# RM_finish.net
KiCad netlist of a schematic drawn in EAGLE
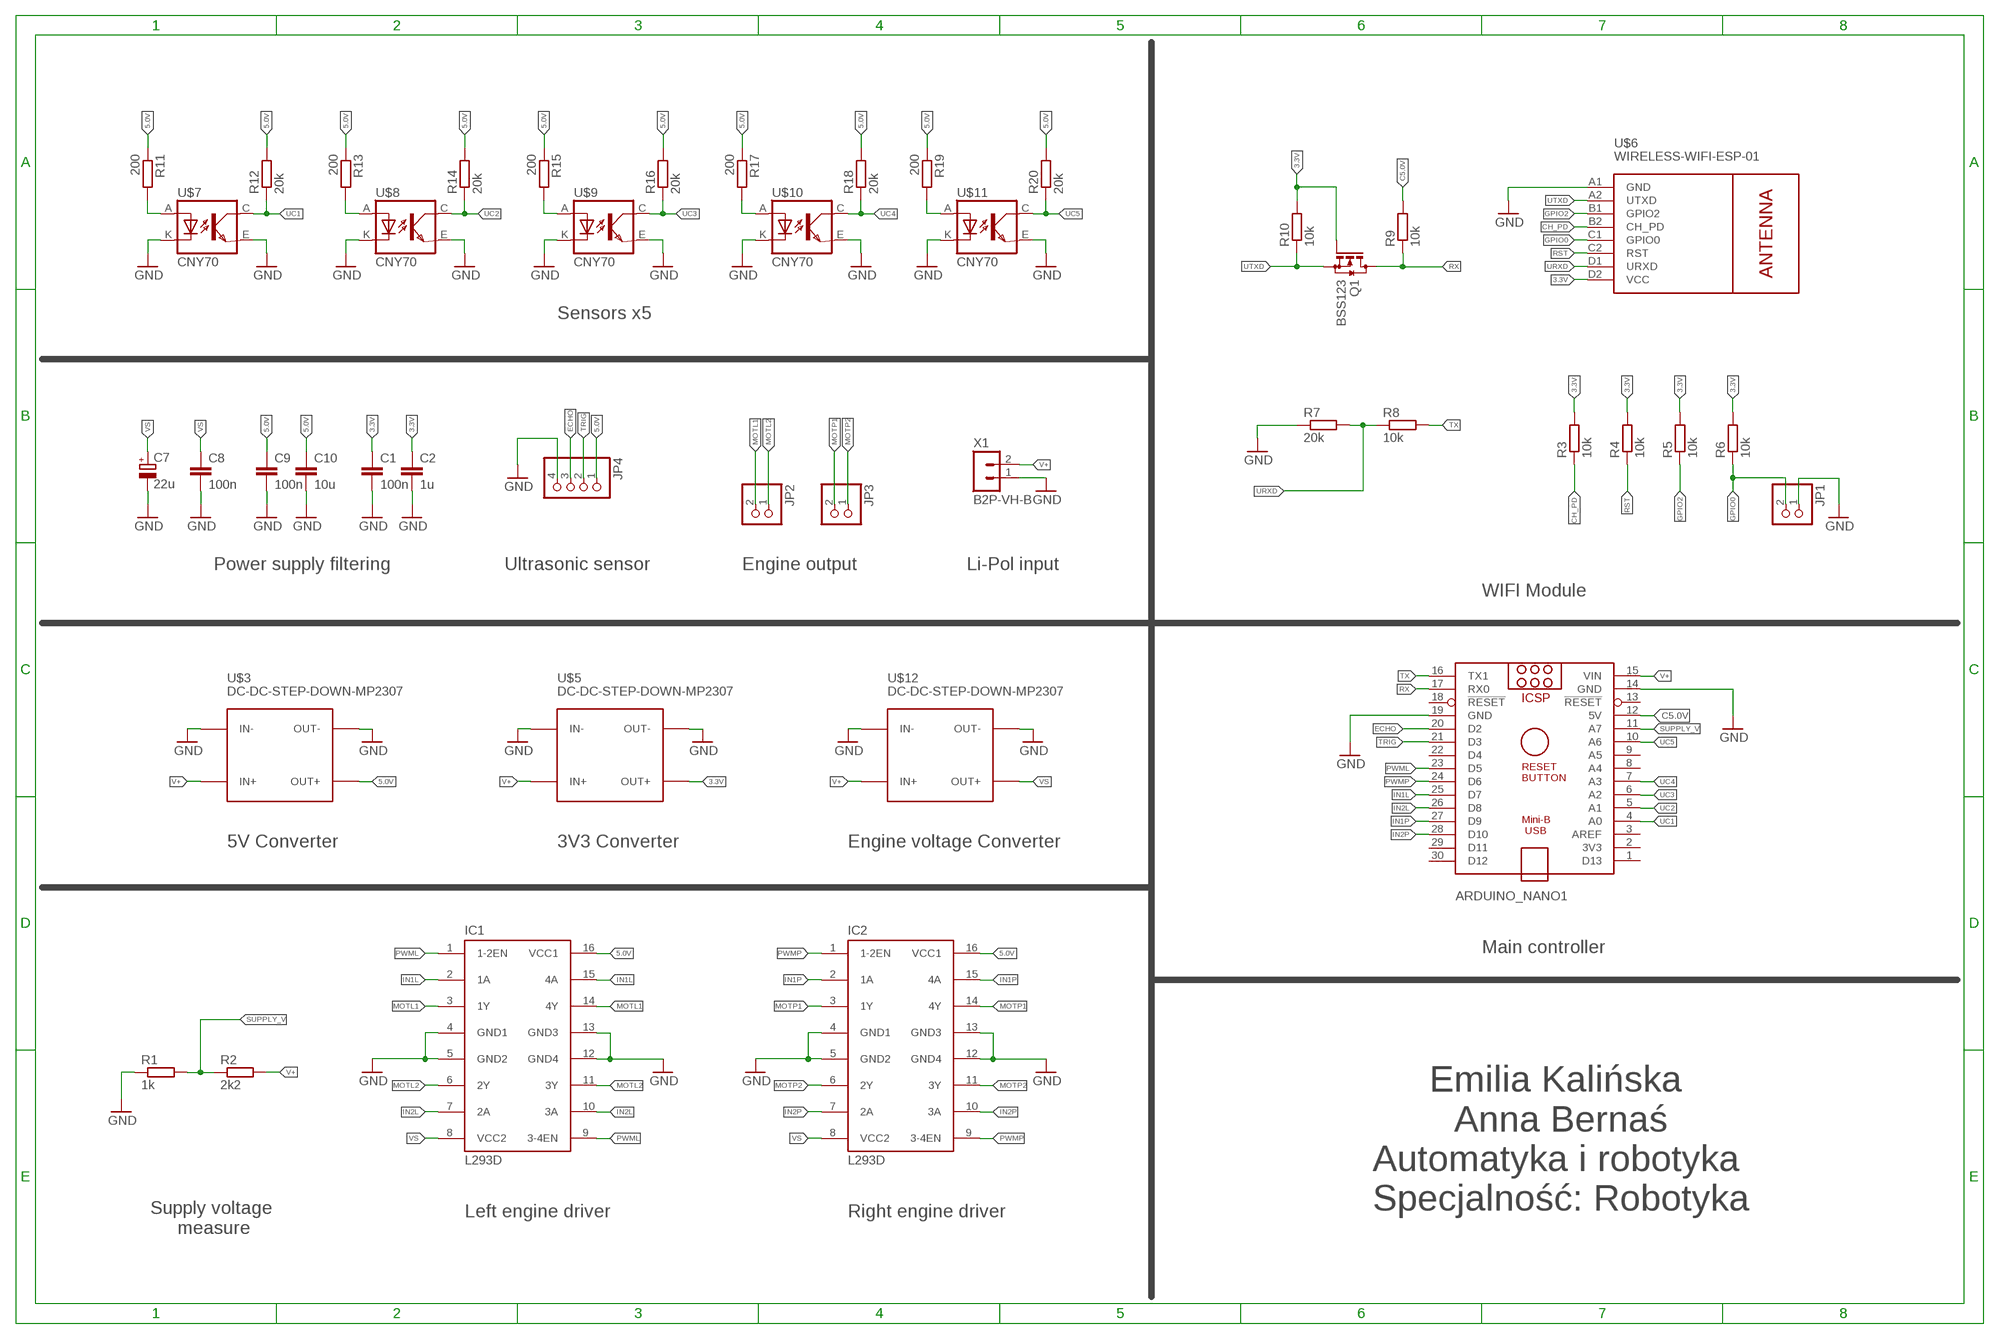
[diagram p0: schematic, sheet 1]

(export (version "E")
  (design (tool "Eeschema 10.0.6"))
  (components
    (comp (ref "ARDUINO_NANO1")
      (value "ARDUINO_NANO")
      (footprint "eagle-import:ARDUINO_NANO")
      (libsource (lib "eagle-import") (part "ARDUINO_NANO"))
    )
    (comp (ref "C1")
      (value "100n")
      (footprint "eagle-import:C0805")
      (libsource (lib "eagle-import") (part "C-EUC0805"))
    )
    (comp (ref "C2")
      (value "1u")
      (footprint "eagle-import:C0805")
      (libsource (lib "eagle-import") (part "C-EUC0805"))
    )
    (comp (ref "C7")
      (value "22u")
      (footprint "eagle-import:153CLV-0405")
      (libsource (lib "eagle-import") (part "CPOL-EU153CLV-0405"))
    )
    (comp (ref "C8")
      (value "100n")
      (footprint "eagle-import:C0805")
      (libsource (lib "eagle-import") (part "C-EUC0805"))
    )
    (comp (ref "C9")
      (value "100n")
      (footprint "eagle-import:C0805")
      (libsource (lib "eagle-import") (part "C-EUC0805"))
    )
    (comp (ref "C10")
      (value "10u")
      (footprint "eagle-import:C0805")
      (libsource (lib "eagle-import") (part "C-EUC0805"))
    )
    (comp (ref "IC1")
      (value "L293D")
      (footprint "eagle-import:DIL16")
      (libsource (lib "eagle-import") (part "L293D"))
    )
    (comp (ref "IC2")
      (value "L293D")
      (footprint "eagle-import:DIL16")
      (libsource (lib "eagle-import") (part "L293D"))
    )
    (comp (ref "JP1")
      (value "PINHD-1X2")
      (footprint "eagle-import:1X02")
      (libsource (lib "eagle-import") (part "PINHD-1X2"))
    )
    (comp (ref "JP2")
      (value "PINHD-1X2")
      (footprint "eagle-import:1X02")
      (libsource (lib "eagle-import") (part "PINHD-1X2"))
    )
    (comp (ref "JP3")
      (value "PINHD-1X2")
      (footprint "eagle-import:1X02")
      (libsource (lib "eagle-import") (part "PINHD-1X2"))
    )
    (comp (ref "JP4")
      (value "PINHD-1X4")
      (footprint "eagle-import:1X04")
      (libsource (lib "eagle-import") (part "PINHD-1X4"))
    )
    (comp (ref "Q1")
      (value "BSS123")
      (footprint "eagle-import:SOT23")
      (libsource (lib "eagle-import") (part "BSS123"))
    )
    (comp (ref "R1")
      (value "1k")
      (footprint "eagle-import:R0805")
      (libsource (lib "eagle-import") (part "R-EU_R0805"))
    )
    (comp (ref "R2")
      (value "2k2")
      (footprint "eagle-import:R0805")
      (libsource (lib "eagle-import") (part "R-EU_R0805"))
    )
    (comp (ref "R3")
      (value "10k")
      (footprint "eagle-import:R0805")
      (libsource (lib "eagle-import") (part "R-EU_R0805"))
    )
    (comp (ref "R4")
      (value "10k")
      (footprint "eagle-import:R0805")
      (libsource (lib "eagle-import") (part "R-EU_R0805"))
    )
    (comp (ref "R5")
      (value "10k")
      (footprint "eagle-import:R0805")
      (libsource (lib "eagle-import") (part "R-EU_R0805"))
    )
    (comp (ref "R6")
      (value "10k")
      (footprint "eagle-import:R0805")
      (libsource (lib "eagle-import") (part "R-EU_R0805"))
    )
    (comp (ref "R7")
      (value "20k")
      (footprint "eagle-import:R0805")
      (libsource (lib "eagle-import") (part "R-EU_R0805"))
    )
    (comp (ref "R8")
      (value "10k")
      (footprint "eagle-import:R0805")
      (libsource (lib "eagle-import") (part "R-EU_R0805"))
    )
    (comp (ref "R9")
      (value "10k")
      (footprint "eagle-import:R0805")
      (libsource (lib "eagle-import") (part "R-EU_R0805"))
    )
    (comp (ref "R10")
      (value "10k")
      (footprint "eagle-import:R0805")
      (libsource (lib "eagle-import") (part "R-EU_R0805"))
    )
    (comp (ref "R11")
      (value "200")
      (footprint "eagle-import:R0805")
      (libsource (lib "eagle-import") (part "R-EU_R0805"))
    )
    (comp (ref "R12")
      (value "20k")
      (footprint "eagle-import:R0805")
      (libsource (lib "eagle-import") (part "R-EU_R0805"))
    )
    (comp (ref "R13")
      (value "200")
      (footprint "eagle-import:R0805")
      (libsource (lib "eagle-import") (part "R-EU_R0805"))
    )
    (comp (ref "R14")
      (value "20k")
      (footprint "eagle-import:R0805")
      (libsource (lib "eagle-import") (part "R-EU_R0805"))
    )
    (comp (ref "R15")
      (value "200")
      (footprint "eagle-import:R0805")
      (libsource (lib "eagle-import") (part "R-EU_R0805"))
    )
    (comp (ref "R16")
      (value "20k")
      (footprint "eagle-import:R0805")
      (libsource (lib "eagle-import") (part "R-EU_R0805"))
    )
    (comp (ref "R17")
      (value "200")
      (footprint "eagle-import:R0805")
      (libsource (lib "eagle-import") (part "R-EU_R0805"))
    )
    (comp (ref "R18")
      (value "20k")
      (footprint "eagle-import:R0805")
      (libsource (lib "eagle-import") (part "R-EU_R0805"))
    )
    (comp (ref "R19")
      (value "200")
      (footprint "eagle-import:R0805")
      (libsource (lib "eagle-import") (part "R-EU_R0805"))
    )
    (comp (ref "R20")
      (value "20k")
      (footprint "eagle-import:R0805")
      (libsource (lib "eagle-import") (part "R-EU_R0805"))
    )
    (comp (ref "U$3")
      (value "DC-DC-STEP-DOWN-MP2307")
      (footprint "eagle-import:DC-DC-STEP-DOWN-MP2307")
      (libsource (lib "eagle-import") (part "DC-DC-STEP-DOWN-MP2307"))
    )
    (comp (ref "U$5")
      (value "DC-DC-STEP-DOWN-MP2307")
      (footprint "eagle-import:DC-DC-STEP-DOWN-MP2307")
      (libsource (lib "eagle-import") (part "DC-DC-STEP-DOWN-MP2307"))
    )
    (comp (ref "U$6")
      (value "WIRELESS-WIFI-ESP-01")
      (footprint "eagle-import:WIRELESS-WIFI-ESP-01")
      (libsource (lib "eagle-import") (part "WIRELESS-WIFI-ESP-01"))
    )
    (comp (ref "U$7")
      (value "CNY70")
      (footprint "eagle-import:4")
      (libsource (lib "eagle-import") (part "CNY70"))
    )
    (comp (ref "U$8")
      (value "CNY70")
      (footprint "eagle-import:4")
      (libsource (lib "eagle-import") (part "CNY70"))
    )
    (comp (ref "U$9")
      (value "CNY70")
      (footprint "eagle-import:4")
      (libsource (lib "eagle-import") (part "CNY70"))
    )
    (comp (ref "U$10")
      (value "CNY70")
      (footprint "eagle-import:4")
      (libsource (lib "eagle-import") (part "CNY70"))
    )
    (comp (ref "U$11")
      (value "CNY70")
      (footprint "eagle-import:4")
      (libsource (lib "eagle-import") (part "CNY70"))
    )
    (comp (ref "U$12")
      (value "DC-DC-STEP-DOWN-MP2307")
      (footprint "eagle-import:DC-DC-STEP-DOWN-MP2307")
      (libsource (lib "eagle-import") (part "DC-DC-STEP-DOWN-MP2307"))
    )
    (comp (ref "X1")
      (value "B2P-VH-B")
      (footprint "eagle-import:B2P-VH")
      (libsource (lib "eagle-import") (part "B2P-VH-B"))
    )
  )
  (nets
    (net (code "1") (name "3.3V") (class "Default")
      (node (ref "C1") (pin "1") (pinfunction "1_1") (pintype "passive"))
      (node (ref "C2") (pin "1") (pinfunction "1_1") (pintype "passive"))
      (node (ref "Q1") (pin "1") (pinfunction "G_1") (pintype "passive"))
      (node (ref "R10") (pin "2") (pinfunction "2_2") (pintype "passive"))
      (node (ref "R3") (pin "2") (pinfunction "2_2") (pintype "passive"))
      (node (ref "R4") (pin "2") (pinfunction "2_2") (pintype "passive"))
      (node (ref "R5") (pin "2") (pinfunction "2_2") (pintype "passive"))
      (node (ref "R6") (pin "2") (pinfunction "2_2") (pintype "passive"))
      (node (ref "U$5") (pin "OUT+") (pinfunction "OUT+_OUT+") (pintype "bidirectional"))
      (node (ref "U$6") (pin "D2") (pinfunction "VCC_D2") (pintype "power_in"))
    )
    (net (code "2") (name "5.0V") (class "Default")
      (node (ref "C10") (pin "1") (pinfunction "1_1") (pintype "passive"))
      (node (ref "C9") (pin "1") (pinfunction "1_1") (pintype "passive"))
      (node (ref "IC1") (pin "16") (pinfunction "VCC1_16") (pintype "power_in"))
      (node (ref "IC2") (pin "16") (pinfunction "VCC1_16") (pintype "power_in"))
      (node (ref "JP4") (pin "1") (pinfunction "1_1") (pintype "passive"))
      (node (ref "R11") (pin "1") (pinfunction "1_1") (pintype "passive"))
      (node (ref "R12") (pin "2") (pinfunction "2_2") (pintype "passive"))
      (node (ref "R13") (pin "1") (pinfunction "1_1") (pintype "passive"))
      (node (ref "R14") (pin "2") (pinfunction "2_2") (pintype "passive"))
      (node (ref "R15") (pin "1") (pinfunction "1_1") (pintype "passive"))
      (node (ref "R16") (pin "2") (pinfunction "2_2") (pintype "passive"))
      (node (ref "R17") (pin "1") (pinfunction "1_1") (pintype "passive"))
      (node (ref "R18") (pin "2") (pinfunction "2_2") (pintype "passive"))
      (node (ref "R19") (pin "1") (pinfunction "1_1") (pintype "passive"))
      (node (ref "R20") (pin "2") (pinfunction "2_2") (pintype "passive"))
      (node (ref "U$3") (pin "OUT+") (pinfunction "OUT+_OUT+") (pintype "bidirectional"))
    )
    (net (code "3") (name "C5.0V") (class "Default")
      (node (ref "ARDUINO_NANO1") (pin "12") (pinfunction "5V_12") (pintype "power_in"))
      (node (ref "R9") (pin "2") (pinfunction "2_2") (pintype "passive"))
    )
    (net (code "4") (name "CH_PD") (class "Default")
      (node (ref "R3") (pin "1") (pinfunction "1_1") (pintype "passive"))
      (node (ref "U$6") (pin "B2") (pinfunction "CH_PD_B2") (pintype "bidirectional"))
    )
    (net (code "5") (name "ECHO") (class "Default")
      (node (ref "ARDUINO_NANO1") (pin "20") (pinfunction "D2_20") (pintype "bidirectional"))
      (node (ref "JP4") (pin "3") (pinfunction "3_3") (pintype "passive"))
    )
    (net (code "6") (name "GND") (class "Default")
      (node (ref "ARDUINO_NANO1") (pin "14") (pinfunction "GND_14") (pintype "power_in"))
      (node (ref "ARDUINO_NANO1") (pin "19") (pinfunction "GND_19") (pintype "power_in"))
      (node (ref "C1") (pin "2") (pinfunction "2_2") (pintype "passive"))
      (node (ref "C10") (pin "2") (pinfunction "2_2") (pintype "passive"))
      (node (ref "C2") (pin "2") (pinfunction "2_2") (pintype "passive"))
      (node (ref "C7") (pin "-") (pinfunction "-_-") (pintype "passive"))
      (node (ref "C8") (pin "2") (pinfunction "2_2") (pintype "passive"))
      (node (ref "C9") (pin "2") (pinfunction "2_2") (pintype "passive"))
      (node (ref "IC1") (pin "12") (pinfunction "GND4_12") (pintype "power_in"))
      (node (ref "IC1") (pin "13") (pinfunction "GND3_13") (pintype "power_in"))
      (node (ref "IC1") (pin "4") (pinfunction "GND1_4") (pintype "power_in"))
      (node (ref "IC1") (pin "5") (pinfunction "GND2_5") (pintype "power_in"))
      (node (ref "IC2") (pin "12") (pinfunction "GND4_12") (pintype "power_in"))
      (node (ref "IC2") (pin "13") (pinfunction "GND3_13") (pintype "power_in"))
      (node (ref "IC2") (pin "4") (pinfunction "GND1_4") (pintype "power_in"))
      (node (ref "IC2") (pin "5") (pinfunction "GND2_5") (pintype "power_in"))
      (node (ref "JP1") (pin "1") (pinfunction "1_1") (pintype "passive"))
      (node (ref "JP4") (pin "4") (pinfunction "4_4") (pintype "passive"))
      (node (ref "R1") (pin "1") (pinfunction "1_1") (pintype "passive"))
      (node (ref "R7") (pin "1") (pinfunction "1_1") (pintype "passive"))
      (node (ref "U$10") (pin "E") (pinfunction "EMI_E") (pintype "passive"))
      (node (ref "U$10") (pin "K") (pinfunction "C_K") (pintype "passive"))
      (node (ref "U$11") (pin "E") (pinfunction "EMI_E") (pintype "passive"))
      (node (ref "U$11") (pin "K") (pinfunction "C_K") (pintype "passive"))
      (node (ref "U$12") (pin "IN-") (pinfunction "IN-_IN-") (pintype "bidirectional"))
      (node (ref "U$12") (pin "OUT-") (pinfunction "OUT-_OUT-") (pintype "bidirectional"))
      (node (ref "U$3") (pin "IN-") (pinfunction "IN-_IN-") (pintype "bidirectional"))
      (node (ref "U$3") (pin "OUT-") (pinfunction "OUT-_OUT-") (pintype "bidirectional"))
      (node (ref "U$5") (pin "IN-") (pinfunction "IN-_IN-") (pintype "bidirectional"))
      (node (ref "U$5") (pin "OUT-") (pinfunction "OUT-_OUT-") (pintype "bidirectional"))
      (node (ref "U$6") (pin "A1") (pinfunction "GND_A1") (pintype "power_in"))
      (node (ref "U$7") (pin "E") (pinfunction "EMI_E") (pintype "passive"))
      (node (ref "U$7") (pin "K") (pinfunction "C_K") (pintype "passive"))
      (node (ref "U$8") (pin "E") (pinfunction "EMI_E") (pintype "passive"))
      (node (ref "U$8") (pin "K") (pinfunction "C_K") (pintype "passive"))
      (node (ref "U$9") (pin "E") (pinfunction "EMI_E") (pintype "passive"))
      (node (ref "U$9") (pin "K") (pinfunction "C_K") (pintype "passive"))
      (node (ref "X1") (pin "1") (pinfunction "1_1") (pintype "passive"))
    )
    (net (code "7") (name "GPIO0") (class "Default")
      (node (ref "JP1") (pin "2") (pinfunction "2_2") (pintype "passive"))
      (node (ref "R6") (pin "1") (pinfunction "1_1") (pintype "passive"))
      (node (ref "U$6") (pin "C1") (pinfunction "GPIO0_C1") (pintype "bidirectional"))
    )
    (net (code "8") (name "GPIO2") (class "Default")
      (node (ref "R5") (pin "1") (pinfunction "1_1") (pintype "passive"))
      (node (ref "U$6") (pin "B1") (pinfunction "GPIO2_B1") (pintype "bidirectional"))
    )
    (net (code "9") (name "IN1L") (class "Default")
      (node (ref "ARDUINO_NANO1") (pin "25") (pinfunction "D7_25") (pintype "bidirectional"))
      (node (ref "IC1") (pin "15") (pinfunction "4A_15") (pintype "input"))
      (node (ref "IC1") (pin "2") (pinfunction "1A_2") (pintype "input"))
    )
    (net (code "10") (name "IN1P") (class "Default")
      (node (ref "ARDUINO_NANO1") (pin "27") (pinfunction "D9_27") (pintype "bidirectional"))
      (node (ref "IC2") (pin "15") (pinfunction "4A_15") (pintype "input"))
      (node (ref "IC2") (pin "2") (pinfunction "1A_2") (pintype "input"))
    )
    (net (code "11") (name "IN2L") (class "Default")
      (node (ref "ARDUINO_NANO1") (pin "26") (pinfunction "D8_26") (pintype "bidirectional"))
      (node (ref "IC1") (pin "10") (pinfunction "3A_10") (pintype "input"))
      (node (ref "IC1") (pin "7") (pinfunction "2A_7") (pintype "input"))
    )
    (net (code "12") (name "IN2P") (class "Default")
      (node (ref "ARDUINO_NANO1") (pin "28") (pinfunction "D10_28") (pintype "bidirectional"))
      (node (ref "IC2") (pin "10") (pinfunction "3A_10") (pintype "input"))
      (node (ref "IC2") (pin "7") (pinfunction "2A_7") (pintype "input"))
    )
    (net (code "13") (name "MOTL1") (class "Default")
      (node (ref "IC1") (pin "14") (pinfunction "4Y_14") (pintype "output"))
      (node (ref "IC1") (pin "3") (pinfunction "1Y_3") (pintype "output"))
      (node (ref "JP2") (pin "2") (pinfunction "2_2") (pintype "passive"))
    )
    (net (code "14") (name "MOTL2") (class "Default")
      (node (ref "IC1") (pin "11") (pinfunction "3Y_11") (pintype "output"))
      (node (ref "IC1") (pin "6") (pinfunction "2Y_6") (pintype "output"))
      (node (ref "JP2") (pin "1") (pinfunction "1_1") (pintype "passive"))
    )
    (net (code "15") (name "MOTP1") (class "Default")
      (node (ref "IC2") (pin "14") (pinfunction "4Y_14") (pintype "output"))
      (node (ref "IC2") (pin "3") (pinfunction "1Y_3") (pintype "output"))
      (node (ref "JP3") (pin "2") (pinfunction "2_2") (pintype "passive"))
    )
    (net (code "16") (name "MOTP2") (class "Default")
      (node (ref "IC2") (pin "11") (pinfunction "3Y_11") (pintype "output"))
      (node (ref "IC2") (pin "6") (pinfunction "2Y_6") (pintype "output"))
      (node (ref "JP3") (pin "1") (pinfunction "1_1") (pintype "passive"))
    )
    (net (code "17") (name "Net-(R11-Pad2)") (class "Default")
      (node (ref "R11") (pin "2") (pinfunction "2_2") (pintype "passive"))
      (node (ref "U$7") (pin "A") (pinfunction "A_A") (pintype "passive"))
    )
    (net (code "18") (name "Net-(R13-Pad2)") (class "Default")
      (node (ref "R13") (pin "2") (pinfunction "2_2") (pintype "passive"))
      (node (ref "U$8") (pin "A") (pinfunction "A_A") (pintype "passive"))
    )
    (net (code "19") (name "Net-(R15-Pad2)") (class "Default")
      (node (ref "R15") (pin "2") (pinfunction "2_2") (pintype "passive"))
      (node (ref "U$9") (pin "A") (pinfunction "A_A") (pintype "passive"))
    )
    (net (code "20") (name "Net-(R17-Pad2)") (class "Default")
      (node (ref "R17") (pin "2") (pinfunction "2_2") (pintype "passive"))
      (node (ref "U$10") (pin "A") (pinfunction "A_A") (pintype "passive"))
    )
    (net (code "21") (name "Net-(R19-Pad2)") (class "Default")
      (node (ref "R19") (pin "2") (pinfunction "2_2") (pintype "passive"))
      (node (ref "U$11") (pin "A") (pinfunction "A_A") (pintype "passive"))
    )
    (net (code "22") (name "PWML") (class "Default")
      (node (ref "ARDUINO_NANO1") (pin "23") (pinfunction "D5_23") (pintype "bidirectional"))
      (node (ref "IC1") (pin "1") (pinfunction "1-2EN_1") (pintype "input"))
      (node (ref "IC1") (pin "9") (pinfunction "3-4EN_9") (pintype "input"))
    )
    (net (code "23") (name "PWMP") (class "Default")
      (node (ref "ARDUINO_NANO1") (pin "24") (pinfunction "D6_24") (pintype "bidirectional"))
      (node (ref "IC2") (pin "1") (pinfunction "1-2EN_1") (pintype "input"))
      (node (ref "IC2") (pin "9") (pinfunction "3-4EN_9") (pintype "input"))
    )
    (net (code "24") (name "RST") (class "Default")
      (node (ref "R4") (pin "1") (pinfunction "1_1") (pintype "passive"))
      (node (ref "U$6") (pin "C2") (pinfunction "RST_C2") (pintype "bidirectional"))
    )
    (net (code "25") (name "RX") (class "Default")
      (node (ref "ARDUINO_NANO1") (pin "17") (pinfunction "RX0_17") (pintype "bidirectional"))
      (node (ref "Q1") (pin "3") (pinfunction "D_3") (pintype "passive"))
      (node (ref "R9") (pin "1") (pinfunction "1_1") (pintype "passive"))
    )
    (net (code "26") (name "SUPPLY_V") (class "Default")
      (node (ref "ARDUINO_NANO1") (pin "11") (pinfunction "A7_11") (pintype "bidirectional"))
      (node (ref "R1") (pin "2") (pinfunction "2_2") (pintype "passive"))
      (node (ref "R2") (pin "1") (pinfunction "1_1") (pintype "passive"))
    )
    (net (code "27") (name "TRIG") (class "Default")
      (node (ref "ARDUINO_NANO1") (pin "21") (pinfunction "D3_21") (pintype "bidirectional"))
      (node (ref "JP4") (pin "2") (pinfunction "2_2") (pintype "passive"))
    )
    (net (code "28") (name "TX") (class "Default")
      (node (ref "ARDUINO_NANO1") (pin "16") (pinfunction "TX1_16") (pintype "bidirectional"))
      (node (ref "R8") (pin "2") (pinfunction "2_2") (pintype "passive"))
    )
    (net (code "29") (name "UC1") (class "Default")
      (node (ref "ARDUINO_NANO1") (pin "4") (pinfunction "A0_4") (pintype "bidirectional"))
      (node (ref "R12") (pin "1") (pinfunction "1_1") (pintype "passive"))
      (node (ref "U$7") (pin "C") (pinfunction "COL_C") (pintype "passive"))
    )
    (net (code "30") (name "UC2") (class "Default")
      (node (ref "ARDUINO_NANO1") (pin "5") (pinfunction "A1_5") (pintype "bidirectional"))
      (node (ref "R14") (pin "1") (pinfunction "1_1") (pintype "passive"))
      (node (ref "U$8") (pin "C") (pinfunction "COL_C") (pintype "passive"))
    )
    (net (code "31") (name "UC3") (class "Default")
      (node (ref "ARDUINO_NANO1") (pin "6") (pinfunction "A2_6") (pintype "bidirectional"))
      (node (ref "R16") (pin "1") (pinfunction "1_1") (pintype "passive"))
      (node (ref "U$9") (pin "C") (pinfunction "COL_C") (pintype "passive"))
    )
    (net (code "32") (name "UC4") (class "Default")
      (node (ref "ARDUINO_NANO1") (pin "7") (pinfunction "A3_7") (pintype "bidirectional"))
      (node (ref "R18") (pin "1") (pinfunction "1_1") (pintype "passive"))
      (node (ref "U$10") (pin "C") (pinfunction "COL_C") (pintype "passive"))
    )
    (net (code "33") (name "UC5") (class "Default")
      (node (ref "ARDUINO_NANO1") (pin "10") (pinfunction "A6_10") (pintype "bidirectional"))
      (node (ref "R20") (pin "1") (pinfunction "1_1") (pintype "passive"))
      (node (ref "U$11") (pin "C") (pinfunction "COL_C") (pintype "passive"))
    )
    (net (code "34") (name "URXD") (class "Default")
      (node (ref "R7") (pin "2") (pinfunction "2_2") (pintype "passive"))
      (node (ref "R8") (pin "1") (pinfunction "1_1") (pintype "passive"))
      (node (ref "U$6") (pin "D1") (pinfunction "URXD_D1") (pintype "bidirectional"))
    )
    (net (code "35") (name "UTXD") (class "Default")
      (node (ref "Q1") (pin "2") (pinfunction "S_2") (pintype "passive"))
      (node (ref "R10") (pin "1") (pinfunction "1_1") (pintype "passive"))
      (node (ref "U$6") (pin "A2") (pinfunction "UTXD_A2") (pintype "bidirectional"))
    )
    (net (code "36") (name "V+") (class "Default")
      (node (ref "ARDUINO_NANO1") (pin "15") (pinfunction "VIN_15") (pintype "power_in"))
      (node (ref "R2") (pin "2") (pinfunction "2_2") (pintype "passive"))
      (node (ref "U$12") (pin "IN+") (pinfunction "IN+_IN+") (pintype "bidirectional"))
      (node (ref "U$3") (pin "IN+") (pinfunction "IN+_IN+") (pintype "bidirectional"))
      (node (ref "U$5") (pin "IN+") (pinfunction "IN+_IN+") (pintype "bidirectional"))
      (node (ref "X1") (pin "2") (pinfunction "2_2") (pintype "passive"))
    )
    (net (code "37") (name "VS") (class "Default")
      (node (ref "C7") (pin "+") (pinfunction "+_+") (pintype "passive"))
      (node (ref "C8") (pin "1") (pinfunction "1_1") (pintype "passive"))
      (node (ref "IC1") (pin "8") (pinfunction "VCC2_8") (pintype "power_in"))
      (node (ref "IC2") (pin "8") (pinfunction "VCC2_8") (pintype "power_in"))
      (node (ref "U$12") (pin "OUT+") (pinfunction "OUT+_OUT+") (pintype "bidirectional"))
    )
    (net (code "38") (name "unconnected-(ARDUINO_NANO1-3V3-Pad2)") (class "Default")
      (node (ref "ARDUINO_NANO1") (pin "2") (pinfunction "3V3_2") (pintype "output"))
    )
    (net (code "39") (name "unconnected-(ARDUINO_NANO1-A4-Pad8)") (class "Default")
      (node (ref "ARDUINO_NANO1") (pin "8") (pinfunction "A4_8") (pintype "bidirectional"))
    )
    (net (code "40") (name "unconnected-(ARDUINO_NANO1-A5-Pad9)") (class "Default")
      (node (ref "ARDUINO_NANO1") (pin "9") (pinfunction "A5_9") (pintype "bidirectional"))
    )
    (net (code "41") (name "unconnected-(ARDUINO_NANO1-AREF-Pad3)") (class "Default")
      (node (ref "ARDUINO_NANO1") (pin "3") (pinfunction "AREF_3") (pintype "input"))
    )
    (net (code "42") (name "unconnected-(ARDUINO_NANO1-D4-Pad22)") (class "Default")
      (node (ref "ARDUINO_NANO1") (pin "22") (pinfunction "D4_22") (pintype "bidirectional"))
    )
    (net (code "43") (name "unconnected-(ARDUINO_NANO1-D11-Pad29)") (class "Default")
      (node (ref "ARDUINO_NANO1") (pin "29") (pinfunction "D11_29") (pintype "bidirectional"))
    )
    (net (code "44") (name "unconnected-(ARDUINO_NANO1-D12-Pad30)") (class "Default")
      (node (ref "ARDUINO_NANO1") (pin "30") (pinfunction "D12_30") (pintype "bidirectional"))
    )
    (net (code "45") (name "unconnected-(ARDUINO_NANO1-D13-Pad1)") (class "Default")
      (node (ref "ARDUINO_NANO1") (pin "1") (pinfunction "D13_1") (pintype "bidirectional"))
    )
    (net (code "46") (name "unconnected-(ARDUINO_NANO1-~{RESET}-Pad13)") (class "Default")
      (node (ref "ARDUINO_NANO1") (pin "13") (pinfunction "~{RESET}_13") (pintype "input"))
    )
    (net (code "47") (name "unconnected-(ARDUINO_NANO1-~{RESET}-Pad18)") (class "Default")
      (node (ref "ARDUINO_NANO1") (pin "18") (pinfunction "~{RESET}_18") (pintype "input"))
    )
  )
)
